# XIAO-log_2-2.net
KiCad netlist of a schematic drawn in Altium Designer
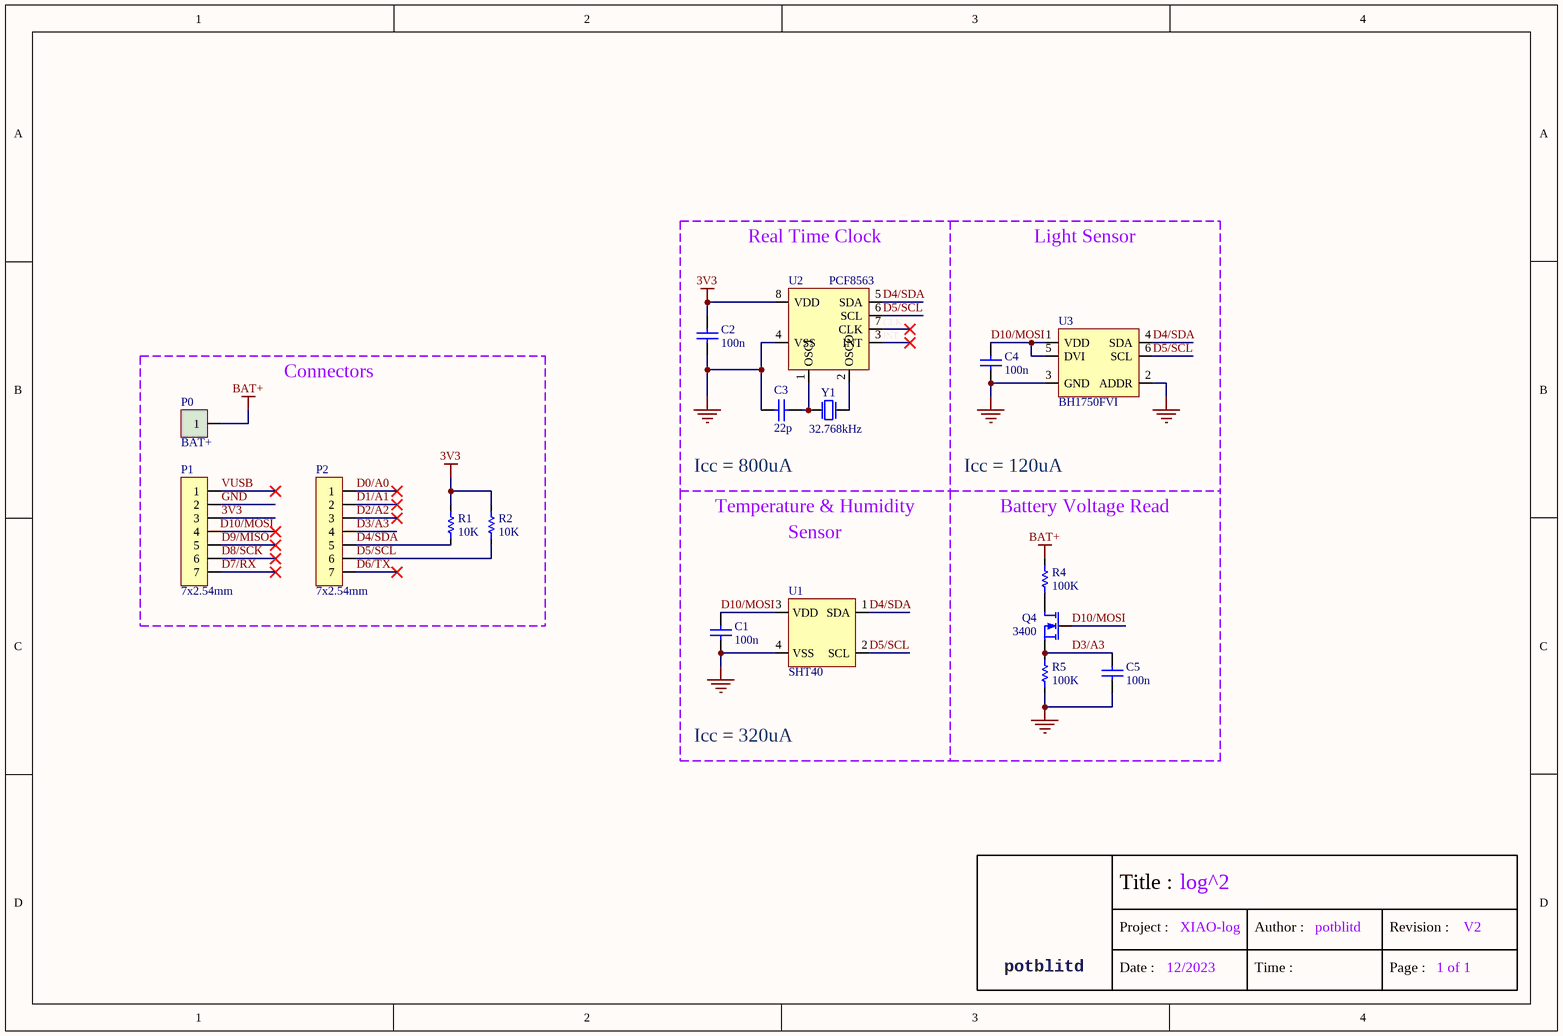
[diagram p0: XIAO-log^2-2.SchDoc]

(export (version "E")
  (design (tool "Eeschema 10.0.6"))
  (components
    (comp (ref "C1")
      (value "100n")
      (footprint "0603CM")
      (description "Capacitor 100nF ±10% 50V")
      (fields (field (name "Comment") "Capacitor"))
      (libsource (lib "Simulation Generic Components") (part "Capacitor"))
    )
    (comp (ref "C2")
      (value "100n")
      (footprint "0603CM")
      (description "Capacitor 100nF ±10% 50V")
      (fields (field (name "Comment") "Capacitor"))
      (libsource (lib "Simulation Generic Components") (part "Capacitor"))
    )
    (comp (ref "C3")
      (value "22p")
      (footprint "0603CM")
      (description "Capacitor 22pF ±5% 50V")
      (fields (field (name "Comment") "Capacitor"))
      (libsource (lib "Simulation Generic Components") (part "Capacitor"))
    )
    (comp (ref "C4")
      (value "100n")
      (footprint "0603CM")
      (description "Capacitor 100nF ±10% 50V")
      (fields (field (name "Comment") "Capacitor"))
      (libsource (lib "Simulation Generic Components") (part "Capacitor"))
    )
    (comp (ref "C5")
      (value "100n")
      (footprint "0603CM")
      (description "Capacitor 100nF ±10% 50V")
      (fields (field (name "Comment") "Capacitor"))
      (libsource (lib "Simulation Generic Components") (part "Capacitor"))
    )
    (comp (ref "P0")
      (value "BAT+")
      (footprint "1P-2.54mm")
      (description "General 2-pin connection")
      (libsource (lib "AltiumLib") (part "1-pin Header"))
    )
    (comp (ref "P1")
      (value "7x2.54mm")
      (footprint "7P-2.54mm-nosilk")
      (description "General 7-pin connection")
      (libsource (lib "AltiumLib") (part "7-pins Header"))
    )
    (comp (ref "P2")
      (value "7x2.54mm")
      (footprint "7P-2.54mm-nosilk")
      (description "General 7-pin connection")
      (libsource (lib "AltiumLib") (part "7-pins Header"))
    )
    (comp (ref "Q4")
      (value "3400")
      (footprint "SOT23-3 M")
      (description "MOSFET N-channel 30V 5.7A")
      (libsource (lib "AltiumLib") (part "MOSFET-N"))
    )
    (comp (ref "R1")
      (value "10K")
      (footprint "0603RM")
      (description "Resistor 10kΩ ±1% 1/16W")
      (fields (field (name "Comment") "Resistor"))
      (libsource (lib "Simulation Generic Components") (part "RES"))
    )
    (comp (ref "R2")
      (value "10K")
      (footprint "0603RM")
      (description "Resistor 10kΩ ±1% 1/16W")
      (fields (field (name "Comment") "Resistor"))
      (libsource (lib "Simulation Generic Components") (part "RES"))
    )
    (comp (ref "R4")
      (value "100K")
      (footprint "0603RM")
      (description "Resistor 100kΩ ±1% 100mW")
      (fields (field (name "Comment") "Resistor"))
      (libsource (lib "Simulation Generic Components") (part "RES"))
    )
    (comp (ref "R5")
      (value "100K")
      (footprint "0603RM")
      (description "Resistor 100kΩ ±1% 100mW")
      (fields (field (name "Comment") "Resistor"))
      (libsource (lib "Simulation Generic Components") (part "RES"))
    )
    (comp (ref "U1")
      (value "SHT40")
      (footprint "DFN-4-EP(1.5x1.5) M")
      (description "SHT40 temperature and humidity sensor")
      (libsource (lib "AltiumLib") (part "SHT40"))
    )
    (comp (ref "U2")
      (value "PCF8563")
      (footprint "SOP-8 M")
      (description "IC real-time clock with alarm interrupt")
      (libsource (lib "AltiumLib") (part "RTC-8563"))
    )
    (comp (ref "U3")
      (value "BH1750FVI")
      (footprint "WSOF6 M")
      (description "Digital light sensor")
      (libsource (lib "AltiumLib") (part "BH1750"))
    )
    (comp (ref "Y1")
      (value "32.768kHz")
      (footprint "FC135 M")
      (description "Crystal oscillator 32.768kHz 20ppm 12.5pF")
      (fields (field (name "Comment") "Oscillator"))
      (libsource (lib "AltiumLib") (part "XO-2"))
    )
  )
  (nets
    (net (code "1") (name "/CLK") (class "Default")
      (node (ref "U2") (pin "7") (pinfunction "CLK_7") (pintype "passive+no_connect"))
    )
    (net (code "2") (name "/D0{slash}A0") (class "Default")
      (node (ref "P2") (pin "1") (pinfunction "1_1") (pintype "passive+no_connect"))
    )
    (net (code "3") (name "/D1{slash}A1") (class "Default")
      (node (ref "P2") (pin "2") (pinfunction "2_2") (pintype "passive+no_connect"))
    )
    (net (code "4") (name "/D2{slash}A2") (class "Default")
      (node (ref "P2") (pin "3") (pinfunction "3_3") (pintype "passive+no_connect"))
    )
    (net (code "5") (name "/D3{slash}A3") (class "Default")
      (node (ref "C5") (pin "1") (pinfunction "1_1") (pintype "passive"))
      (node (ref "P2") (pin "4") (pinfunction "4_4") (pintype "passive"))
      (node (ref "Q4") (pin "2") (pinfunction "S_2") (pintype "passive"))
      (node (ref "R5") (pin "2") (pinfunction "2_2") (pintype "passive"))
    )
    (net (code "6") (name "/D4{slash}SDA") (class "Default")
      (node (ref "P2") (pin "5") (pinfunction "5_5") (pintype "passive"))
      (node (ref "R1") (pin "1") (pinfunction "1_1") (pintype "passive"))
      (node (ref "U1") (pin "1") (pinfunction "SDA_1") (pintype "passive"))
      (node (ref "U2") (pin "5") (pinfunction "SDA_5") (pintype "passive"))
      (node (ref "U3") (pin "4") (pinfunction "SDA_4") (pintype "passive"))
    )
    (net (code "7") (name "/D5{slash}SCL") (class "Default")
      (node (ref "P2") (pin "6") (pinfunction "6_6") (pintype "passive"))
      (node (ref "R2") (pin "1") (pinfunction "1_1") (pintype "passive"))
      (node (ref "U1") (pin "2") (pinfunction "SCL_2") (pintype "passive"))
      (node (ref "U2") (pin "6") (pinfunction "SCL_6") (pintype "passive"))
      (node (ref "U3") (pin "6") (pinfunction "SCL_6") (pintype "passive"))
    )
    (net (code "8") (name "/D6{slash}TX") (class "Default")
      (node (ref "P2") (pin "7") (pinfunction "7_7") (pintype "passive+no_connect"))
    )
    (net (code "9") (name "/D7{slash}RX") (class "Default")
      (node (ref "P1") (pin "7") (pinfunction "7_7") (pintype "passive+no_connect"))
    )
    (net (code "10") (name "/D8{slash}SCK") (class "Default")
      (node (ref "P1") (pin "6") (pinfunction "6_6") (pintype "passive+no_connect"))
    )
    (net (code "11") (name "/D9{slash}MISO") (class "Default")
      (node (ref "P1") (pin "5") (pinfunction "5_5") (pintype "passive+no_connect"))
    )
    (net (code "12") (name "/D10{slash}MOSI") (class "Default")
      (node (ref "C1") (pin "1") (pinfunction "1_1") (pintype "passive"))
      (node (ref "C4") (pin "1") (pinfunction "1_1") (pintype "passive"))
      (node (ref "P1") (pin "4") (pinfunction "4_4") (pintype "passive"))
      (node (ref "Q4") (pin "1") (pinfunction "G_1") (pintype "passive"))
      (node (ref "U1") (pin "3") (pinfunction "VDD_3") (pintype "passive"))
      (node (ref "U3") (pin "1") (pinfunction "VDD_1") (pintype "passive"))
      (node (ref "U3") (pin "5") (pinfunction "DVI_5") (pintype "passive"))
    )
    (net (code "13") (name "/INT") (class "Default")
      (node (ref "U2") (pin "3") (pinfunction "INT_3") (pintype "passive+no_connect"))
    )
    (net (code "14") (name "/VUSB") (class "Default")
      (node (ref "P1") (pin "1") (pinfunction "1_1") (pintype "passive+no_connect"))
    )
    (net (code "15") (name "3V3") (class "Default")
      (node (ref "C2") (pin "1") (pinfunction "1_1") (pintype "passive"))
      (node (ref "P1") (pin "3") (pinfunction "3_3") (pintype "passive"))
      (node (ref "R1") (pin "2") (pinfunction "2_2") (pintype "passive"))
      (node (ref "R2") (pin "2") (pinfunction "2_2") (pintype "passive"))
      (node (ref "U2") (pin "8") (pinfunction "VDD_8") (pintype "passive"))
    )
    (net (code "16") (name "BAT+") (class "Default")
      (node (ref "P0") (pin "1") (pinfunction "1_1") (pintype "passive"))
      (node (ref "R4") (pin "2") (pinfunction "2_2") (pintype "passive"))
    )
    (net (code "17") (name "GND") (class "Default")
      (node (ref "C1") (pin "2") (pinfunction "2_2") (pintype "passive"))
      (node (ref "C2") (pin "2") (pinfunction "2_2") (pintype "passive"))
      (node (ref "C3") (pin "2") (pinfunction "2_2") (pintype "passive"))
      (node (ref "C4") (pin "2") (pinfunction "2_2") (pintype "passive"))
      (node (ref "C5") (pin "2") (pinfunction "2_2") (pintype "passive"))
      (node (ref "P1") (pin "2") (pinfunction "2_2") (pintype "passive"))
      (node (ref "R5") (pin "1") (pinfunction "1_1") (pintype "passive"))
      (node (ref "U1") (pin "4") (pinfunction "VSS_4") (pintype "passive"))
      (node (ref "U2") (pin "4") (pinfunction "VSS_4") (pintype "passive"))
      (node (ref "U3") (pin "2") (pinfunction "ADDR_2") (pintype "passive"))
      (node (ref "U3") (pin "3") (pinfunction "GND_3") (pintype "passive"))
    )
    (net (code "18") (name "Net-(Q4-D)") (class "Default")
      (node (ref "Q4") (pin "3") (pinfunction "D_3") (pintype "passive"))
      (node (ref "R4") (pin "1") (pinfunction "1_1") (pintype "passive"))
    )
    (net (code "19") (name "Net-(U2-OSCI)") (class "Default")
      (node (ref "C3") (pin "1") (pinfunction "1_1") (pintype "passive"))
      (node (ref "U2") (pin "1") (pinfunction "OSCI_1") (pintype "passive"))
      (node (ref "Y1") (pin "2") (pinfunction "2_2") (pintype "passive"))
    )
    (net (code "20") (name "Net-(U2-OSCO)") (class "Default")
      (node (ref "U2") (pin "2") (pinfunction "OSCO_2") (pintype "passive"))
      (node (ref "Y1") (pin "1") (pinfunction "1_1") (pintype "passive"))
    )
  )
)
